# LAMEBOY.net
KiCad netlist of a schematic drawn in EAGLE
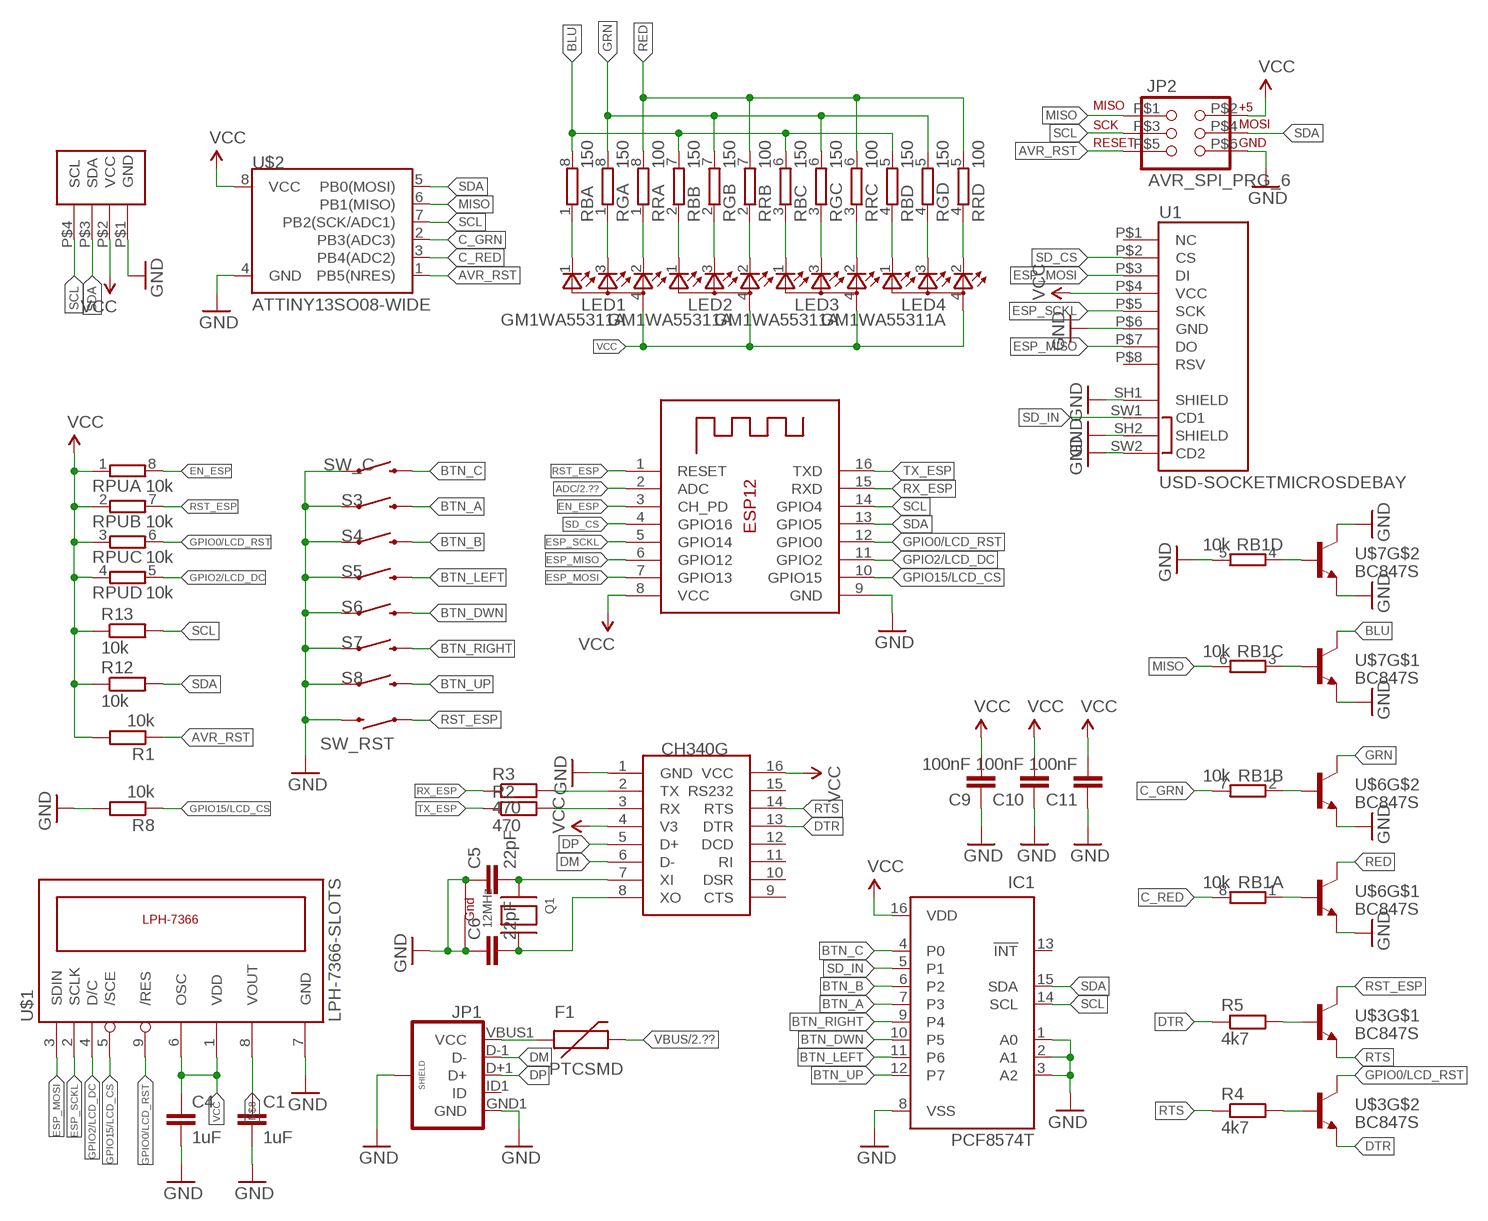
[diagram p0: schematic, sheet 1]
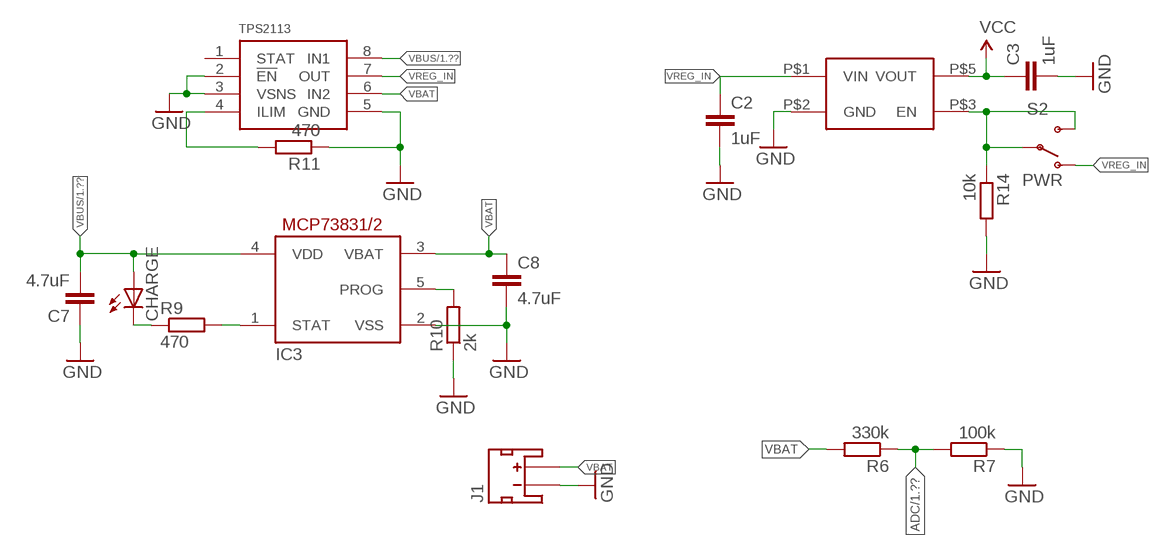
[diagram p1: schematic, sheet 2]

(export (version "E")
  (design (tool "Eeschema 10.0.6"))
  (components
    (comp (ref "C1")
      (value "1uF")
      (footprint "eagle-import:ONEFITSALL")
      (libsource (lib "eagle-import") (part "C-EUONEFITSALL"))
    )
    (comp (ref "C4")
      (value "1uF")
      (footprint "eagle-import:ONEFITSALL")
      (libsource (lib "eagle-import") (part "C-EUONEFITSALL"))
    )
    (comp (ref "C5")
      (value "22pF")
      (footprint "eagle-import:ONEFITSALL")
      (libsource (lib "eagle-import") (part "C-EUONEFITSALL"))
    )
    (comp (ref "C6")
      (value "22pF")
      (footprint "eagle-import:ONEFITSALL")
      (libsource (lib "eagle-import") (part "C-EUONEFITSALL"))
    )
    (comp (ref "C9")
      (value "100nF")
      (footprint "eagle-import:ONEFITSALL")
      (libsource (lib "eagle-import") (part "C-EUONEFITSALL"))
    )
    (comp (ref "C10")
      (value "100nF")
      (footprint "eagle-import:ONEFITSALL")
      (libsource (lib "eagle-import") (part "C-EUONEFITSALL"))
    )
    (comp (ref "C11")
      (value "100nF")
      (footprint "eagle-import:ONEFITSALL")
      (libsource (lib "eagle-import") (part "C-EUONEFITSALL"))
    )
    (comp (ref "CH340G")
      (value "CH340GCH340G")
      (footprint "eagle-import:SOIC16")
      (libsource (lib "eagle-import") (part "CH340GCH340G"))
    )
    (comp (ref "F1")
      (value "PTCSMD")
      (footprint "eagle-import:PTC-1206")
      (libsource (lib "eagle-import") (part "PTCSMD"))
    )
    (comp (ref "IC1")
      (value "PCF8574T")
      (footprint "eagle-import:SO16W")
      (fields (field (name "MPN") "PCF8574T/3,512"))
      (libsource (lib "eagle-import") (part "PCF8574T"))
    )
    (comp (ref "JP1")
      (value "USB_MICROB_PLUG-IDK")
      (footprint "eagle-import:USB-AB-MICRO-SMD_SLOT")
      (libsource (lib "eagle-import") (part "USB_MICROB_PLUG-IDK"))
    )
    (comp (ref "JP2")
      (value "AVR_SPI_PRG_6")
      (footprint "eagle-import:2X3_SMD_PAD")
      (libsource (lib "eagle-import") (part "AVR_SPI_PRG_6"))
    )
    (comp (ref "LED1")
      (value "GM1WA55311A")
      (footprint "eagle-import:GM1WA55311A")
      (libsource (lib "eagle-import") (part "GM1WA55311A"))
    )
    (comp (ref "LED2")
      (value "GM1WA55311A")
      (footprint "eagle-import:GM1WA55311A")
      (libsource (lib "eagle-import") (part "GM1WA55311A"))
    )
    (comp (ref "LED3")
      (value "GM1WA55311A")
      (footprint "eagle-import:GM1WA55311A")
      (libsource (lib "eagle-import") (part "GM1WA55311A"))
    )
    (comp (ref "LED4")
      (value "GM1WA55311A")
      (footprint "eagle-import:GM1WA55311A")
      (libsource (lib "eagle-import") (part "GM1WA55311A"))
    )
    (comp (ref "Q1")
      (value "12MHz")
      (footprint "eagle-import:NX3225_BIGGER")
      (libsource (lib "eagle-import") (part "XTAL-4BIGGER"))
    )
    (comp (ref "R1")
      (value "10k")
      (footprint "eagle-import:ONEFITSALL")
      (libsource (lib "eagle-import") (part "R-EU_ONEFITSALL"))
    )
    (comp (ref "R2")
      (value "470")
      (footprint "eagle-import:ONEFITSALL")
      (libsource (lib "eagle-import") (part "R-EU_ONEFITSALL"))
    )
    (comp (ref "R3")
      (value "470")
      (footprint "eagle-import:ONEFITSALL")
      (libsource (lib "eagle-import") (part "R-EU_ONEFITSALL"))
    )
    (comp (ref "R4")
      (value "4k7")
      (footprint "eagle-import:ONEFITSALL")
      (libsource (lib "eagle-import") (part "R-EU_ONEFITSALL"))
    )
    (comp (ref "R5")
      (value "4k7")
      (footprint "eagle-import:ONEFITSALL")
      (libsource (lib "eagle-import") (part "R-EU_ONEFITSALL"))
    )
    (comp (ref "R8")
      (value "10k")
      (footprint "eagle-import:ONEFITSALL")
      (libsource (lib "eagle-import") (part "R-EU_ONEFITSALL"))
    )
    (comp (ref "R12")
      (value "10k")
      (footprint "eagle-import:ONEFITSALL")
      (libsource (lib "eagle-import") (part "R-EU_ONEFITSALL"))
    )
    (comp (ref "R13")
      (value "10k")
      (footprint "eagle-import:ONEFITSALL")
      (libsource (lib "eagle-import") (part "R-EU_ONEFITSALL"))
    )
    (comp (ref "RB")
      (value "150")
      (footprint "eagle-import:0603-ARC")
      (libsource (lib "eagle-import") (part "4R-N0603-ARC"))
    )
    (comp (ref "RB1")
      (value "10k")
      (footprint "eagle-import:0603-ARC")
      (libsource (lib "eagle-import") (part "4R-N0603-ARC"))
    )
    (comp (ref "RG")
      (value "150")
      (footprint "eagle-import:0603-ARC")
      (libsource (lib "eagle-import") (part "4R-N0603-ARC"))
    )
    (comp (ref "RPU")
      (value "10k")
      (footprint "eagle-import:0603-ARC")
      (libsource (lib "eagle-import") (part "4R-N0603-ARC"))
    )
    (comp (ref "RR")
      (value "100")
      (footprint "eagle-import:0603-ARC")
      (libsource (lib "eagle-import") (part "4R-N0603-ARC"))
    )
    (comp (ref "S3")
      (value "SWITCH-MOMENTARY-2SMD-4")
      (footprint "eagle-import:TACTILE_SWITCH_TALL")
      (libsource (lib "eagle-import") (part "SWITCH-MOMENTARY-2SMD-4"))
    )
    (comp (ref "S4")
      (value "SWITCH-MOMENTARY-2SMD-4")
      (footprint "eagle-import:TACTILE_SWITCH_TALL")
      (libsource (lib "eagle-import") (part "SWITCH-MOMENTARY-2SMD-4"))
    )
    (comp (ref "S5")
      (value "SWITCH-MOMENTARY-2SMD-4")
      (footprint "eagle-import:TACTILE_SWITCH_TALL")
      (libsource (lib "eagle-import") (part "SWITCH-MOMENTARY-2SMD-4"))
    )
    (comp (ref "S6")
      (value "SWITCH-MOMENTARY-2SMD-4")
      (footprint "eagle-import:TACTILE_SWITCH_TALL")
      (libsource (lib "eagle-import") (part "SWITCH-MOMENTARY-2SMD-4"))
    )
    (comp (ref "S7")
      (value "SWITCH-MOMENTARY-2SMD-4")
      (footprint "eagle-import:TACTILE_SWITCH_TALL")
      (libsource (lib "eagle-import") (part "SWITCH-MOMENTARY-2SMD-4"))
    )
    (comp (ref "S8")
      (value "SWITCH-MOMENTARY-2SMD-4")
      (footprint "eagle-import:TACTILE_SWITCH_TALL")
      (libsource (lib "eagle-import") (part "SWITCH-MOMENTARY-2SMD-4"))
    )
    (comp (ref "SW_C")
      (value "SWITCH-MOMENTARY-2-SMD-1101NE")
      (footprint "eagle-import:TACTILE-SWITCH-1101NE")
      (libsource (lib "eagle-import") (part "SWITCH-MOMENTARY-2-SMD-1101NE"))
    )
    (comp (ref "SW_RST")
      (value "SWITCH-MOMENTARY-2-SMD-1101NE")
      (footprint "eagle-import:TACTILE-SWITCH-1101NE")
      (libsource (lib "eagle-import") (part "SWITCH-MOMENTARY-2-SMD-1101NE"))
    )
    (comp (ref "U$1")
      (value "LPH-7366-SLOTS")
      (footprint "eagle-import:LPH-7366-SLOTS")
      (libsource (lib "eagle-import") (part "LPH-7366-SLOTS"))
    )
    (comp (ref "U$2")
      (value "ATTINY13SO08-WIDE")
      (footprint "eagle-import:SO08-EIAJ")
      (libsource (lib "eagle-import") (part "ATTINY13SO08-WIDE"))
    )
    (comp (ref "U$3")
      (value "BC847S")
      (footprint "eagle-import:SOT363")
      (libsource (lib "eagle-import") (part "MMDT3904"))
    )
    (comp (ref "U$6")
      (value "BC847S")
      (footprint "eagle-import:SOT363")
      (libsource (lib "eagle-import") (part "MMDT3904"))
    )
    (comp (ref "U$7")
      (value "BC847S")
      (footprint "eagle-import:SOT363")
      (libsource (lib "eagle-import") (part "MMDT3904"))
    )
    (comp (ref "U$10")
      (value "I2C_GROVE")
      (footprint "eagle-import:I2C_GROVE")
      (libsource (lib "eagle-import") (part "I2C_GROVE"))
    )
    (comp (ref "U1")
      (value "USD-SOCKETMICROSDEBAY")
      (footprint "eagle-import:MICRO-SD-SOCKET-EBAY")
      (libsource (lib "eagle-import") (part "USD-SOCKETMICROSDEBAY"))
    )
    (comp (ref "X1")
      (value "ESP-12")
      (footprint "eagle-import:ESP-12")
      (libsource (lib "eagle-import") (part "ESP-12"))
    )
    (comp (ref "C2")
      (value "1uF")
      (footprint "eagle-import:ONEFITSALL")
      (libsource (lib "eagle-import") (part "C-EUONEFITSALL"))
    )
    (comp (ref "C3")
      (value "1uF")
      (footprint "eagle-import:ONEFITSALL")
      (libsource (lib "eagle-import") (part "C-EUONEFITSALL"))
    )
    (comp (ref "C7")
      (value "4.7uF")
      (footprint "eagle-import:ONEFITSALL")
      (libsource (lib "eagle-import") (part "C-EUONEFITSALL"))
    )
    (comp (ref "C8")
      (value "4.7uF")
      (footprint "eagle-import:ONEFITSALL")
      (libsource (lib "eagle-import") (part "C-EUONEFITSALL"))
    )
    (comp (ref "CHARGE")
      (value "LEDCHARLIE")
      (footprint "eagle-import:CHIPLED_0603_CHARLIE")
      (libsource (lib "eagle-import") (part "LEDCHARLIE"))
    )
    (comp (ref "IC3")
      (value "MCP73831")
      (footprint "eagle-import:SOT23-5L")
      (libsource (lib "eagle-import") (part "MCP73831/OT"))
    )
    (comp (ref "J1")
      (value "JST_2MM_MALE")
      (footprint "eagle-import:JST-2-SMD")
      (libsource (lib "eagle-import") (part "JST_2MM_MALE"))
    )
    (comp (ref "R6")
      (value "330k")
      (footprint "eagle-import:ONEFITSALL")
      (libsource (lib "eagle-import") (part "R-EU_ONEFITSALL"))
    )
    (comp (ref "R7")
      (value "100k")
      (footprint "eagle-import:ONEFITSALL")
      (libsource (lib "eagle-import") (part "R-EU_ONEFITSALL"))
    )
    (comp (ref "R9")
      (value "470")
      (footprint "eagle-import:ONEFITSALL")
      (libsource (lib "eagle-import") (part "R-EU_ONEFITSALL"))
    )
    (comp (ref "R10")
      (value "2k")
      (footprint "eagle-import:ONEFITSALL")
      (libsource (lib "eagle-import") (part "R-EU_ONEFITSALL"))
    )
    (comp (ref "R11")
      (value "470")
      (footprint "eagle-import:ONEFITSALL")
      (libsource (lib "eagle-import") (part "R-EU_ONEFITSALL"))
    )
    (comp (ref "R14")
      (value "10k")
      (footprint "eagle-import:ONEFITSALL")
      (libsource (lib "eagle-import") (part "R-EU_ONEFITSALL"))
    )
    (comp (ref "S2")
      (value "PWR")
      (footprint "eagle-import:SWITCH-SPST-SMD-A")
      (libsource (lib "eagle-import") (part "SWITCH-SPDT-SMD-A"))
    )
    (comp (ref "U$4")
      (value "TPS2113-PW")
      (footprint "eagle-import:TEXAS-PW")
      (libsource (lib "eagle-import") (part "TPS2113-PW"))
    )
    (comp (ref "U$9")
      (value "AP2112KAP2112K")
      (footprint "eagle-import:AP2112")
      (libsource (lib "eagle-import") (part "AP2112KAP2112K"))
    )
  )
  (nets
    (net (code "1") (name "ADC") (class "Default")
      (node (ref "R6") (pin "P$1") (pinfunction "1_P$1") (pintype "passive"))
      (node (ref "R7") (pin "P$2") (pinfunction "2_P$2") (pintype "passive"))
      (node (ref "X1") (pin "2") (pinfunction "ADC_2") (pintype "passive"))
    )
    (net (code "2") (name "AVR_RST") (class "Default")
      (node (ref "JP2") (pin "P$5") (pinfunction "5_P$5") (pintype "passive"))
      (node (ref "R1") (pin "P$1") (pinfunction "1_P$1") (pintype "passive"))
      (node (ref "U$2") (pin "1") (pinfunction "PB5(NRES)_1") (pintype "bidirectional"))
    )
    (net (code "3") (name "BLU") (class "Default")
      (node (ref "RB") (pin "5") (pinfunction "2_5") (pintype "passive"))
      (node (ref "RB") (pin "6") (pinfunction "2_6") (pintype "passive"))
      (node (ref "RB") (pin "7") (pinfunction "2_7") (pintype "passive"))
      (node (ref "RB") (pin "8") (pinfunction "2_8") (pintype "passive"))
      (node (ref "U$7") (pin "3") (pinfunction "C_3") (pintype "passive"))
    )
    (net (code "4") (name "BTN_A") (class "Default")
      (node (ref "IC1") (pin "7") (pinfunction "P3_7") (pintype "bidirectional"))
      (node (ref "S3") (pin "B2") (pinfunction "2_B2") (pintype "passive"))
    )
    (net (code "5") (name "BTN_B") (class "Default")
      (node (ref "IC1") (pin "6") (pinfunction "P2_6") (pintype "bidirectional"))
      (node (ref "S4") (pin "B2") (pinfunction "2_B2") (pintype "passive"))
    )
    (net (code "6") (name "BTN_C") (class "Default")
      (node (ref "IC1") (pin "4") (pinfunction "P0_4") (pintype "bidirectional"))
      (node (ref "SW_C") (pin "P$2") (pinfunction "2_P$2") (pintype "passive"))
    )
    (net (code "7") (name "BTN_DWN") (class "Default")
      (node (ref "IC1") (pin "10") (pinfunction "P5_10") (pintype "bidirectional"))
      (node (ref "S6") (pin "B2") (pinfunction "2_B2") (pintype "passive"))
    )
    (net (code "8") (name "BTN_LEFT") (class "Default")
      (node (ref "IC1") (pin "11") (pinfunction "P6_11") (pintype "bidirectional"))
      (node (ref "S5") (pin "B2") (pinfunction "2_B2") (pintype "passive"))
    )
    (net (code "9") (name "BTN_RIGHT") (class "Default")
      (node (ref "IC1") (pin "9") (pinfunction "P4_9") (pintype "bidirectional"))
      (node (ref "S7") (pin "B2") (pinfunction "2_B2") (pintype "passive"))
    )
    (net (code "10") (name "BTN_UP") (class "Default")
      (node (ref "IC1") (pin "12") (pinfunction "P7_12") (pintype "bidirectional"))
      (node (ref "S8") (pin "B2") (pinfunction "2_B2") (pintype "passive"))
    )
    (net (code "11") (name "C_GRN") (class "Default")
      (node (ref "RB1") (pin "7") (pinfunction "2_7") (pintype "passive"))
      (node (ref "U$2") (pin "2") (pinfunction "PB3(ADC3)_2") (pintype "bidirectional"))
    )
    (net (code "12") (name "C_RED") (class "Default")
      (node (ref "RB1") (pin "8") (pinfunction "2_8") (pintype "passive"))
      (node (ref "U$2") (pin "3") (pinfunction "PB4(ADC2)_3") (pintype "bidirectional"))
    )
    (net (code "13") (name "DM") (class "Default")
      (node (ref "CH340G") (pin "6") (pinfunction "D-_6") (pintype "bidirectional"))
      (node (ref "JP1") (pin "D-1") (pinfunction "D-_D-1") (pintype "bidirectional"))
    )
    (net (code "14") (name "DP") (class "Default")
      (node (ref "CH340G") (pin "5") (pinfunction "D+_5") (pintype "bidirectional"))
      (node (ref "JP1") (pin "D+1") (pinfunction "D+_D+1") (pintype "bidirectional"))
    )
    (net (code "15") (name "DTR") (class "Default")
      (node (ref "CH340G") (pin "13") (pinfunction "DTR_13") (pintype "bidirectional"))
      (node (ref "R5") (pin "P$1") (pinfunction "1_P$1") (pintype "passive"))
      (node (ref "U$3") (pin "1") (pinfunction "E_1") (pintype "passive"))
    )
    (net (code "16") (name "EN_ESP") (class "Default")
      (node (ref "RPU") (pin "8") (pinfunction "2_8") (pintype "passive"))
      (node (ref "X1") (pin "3") (pinfunction "CH_PD_3") (pintype "input"))
    )
    (net (code "17") (name "ESP_MISO") (class "Default")
      (node (ref "U1") (pin "P$7") (pinfunction "DO_P$7") (pintype "bidirectional"))
      (node (ref "X1") (pin "6") (pinfunction "GPIO12_6") (pintype "bidirectional"))
    )
    (net (code "18") (name "ESP_MOSI") (class "Default")
      (node (ref "U$1") (pin "3") (pinfunction "SDIN_3") (pintype "input"))
      (node (ref "U1") (pin "P$3") (pinfunction "DI_P$3") (pintype "bidirectional"))
      (node (ref "X1") (pin "7") (pinfunction "GPIO13_7") (pintype "bidirectional"))
    )
    (net (code "19") (name "ESP_SCKL") (class "Default")
      (node (ref "U$1") (pin "2") (pinfunction "SCLK_2") (pintype "input"))
      (node (ref "U1") (pin "P$5") (pinfunction "SCK_P$5") (pintype "bidirectional"))
      (node (ref "X1") (pin "5") (pinfunction "GPIO14_5") (pintype "bidirectional"))
    )
    (net (code "20") (name "GND") (class "Default")
      (node (ref "C1") (pin "P$2") (pinfunction "2_P$2") (pintype "passive"))
      (node (ref "C10") (pin "P$1") (pinfunction "1_P$1") (pintype "passive"))
      (node (ref "C11") (pin "P$1") (pinfunction "1_P$1") (pintype "passive"))
      (node (ref "C2") (pin "P$2") (pinfunction "2_P$2") (pintype "passive"))
      (node (ref "C3") (pin "P$2") (pinfunction "2_P$2") (pintype "passive"))
      (node (ref "C4") (pin "P$2") (pinfunction "2_P$2") (pintype "passive"))
      (node (ref "C5") (pin "P$1") (pinfunction "1_P$1") (pintype "passive"))
      (node (ref "C6") (pin "P$1") (pinfunction "1_P$1") (pintype "passive"))
      (node (ref "C7") (pin "P$1") (pinfunction "1_P$1") (pintype "passive"))
      (node (ref "C8") (pin "P$2") (pinfunction "2_P$2") (pintype "passive"))
      (node (ref "C9") (pin "P$1") (pinfunction "1_P$1") (pintype "passive"))
      (node (ref "CH340G") (pin "1") (pinfunction "GND_1") (pintype "bidirectional"))
      (node (ref "IC1") (pin "1") (pinfunction "A0_1") (pintype "input"))
      (node (ref "IC1") (pin "2") (pinfunction "A1_2") (pintype "input"))
      (node (ref "IC1") (pin "3") (pinfunction "A2_3") (pintype "input"))
      (node (ref "IC1") (pin "8") (pinfunction "VSS_8") (pintype "power_in"))
      (node (ref "IC3") (pin "2") (pinfunction "VSS_2") (pintype "power_in"))
      (node (ref "J1") (pin "1") (pinfunction "-_1") (pintype "bidirectional"))
      (node (ref "JP1") (pin "GND1") (pinfunction "GND_GND1") (pintype "bidirectional"))
      (node (ref "JP1") (pin "P$1") (pinfunction "SHIELD_P$1") (pintype "bidirectional"))
      (node (ref "JP1") (pin "P$2") (pinfunction "SHIELD_P$2") (pintype "bidirectional"))
      (node (ref "JP1") (pin "P$3") (pinfunction "SHIELD_P$3") (pintype "bidirectional"))
      (node (ref "JP1") (pin "P$4") (pinfunction "SHIELD_P$4") (pintype "bidirectional"))
      (node (ref "JP2") (pin "P$6") (pinfunction "6_P$6") (pintype "passive"))
      (node (ref "Q1") (pin "2") (pinfunction "G2_2") (pintype "power_in"))
      (node (ref "Q1") (pin "4") (pinfunction "G1_4") (pintype "power_in"))
      (node (ref "R10") (pin "P$1") (pinfunction "1_P$1") (pintype "passive"))
      (node (ref "R11") (pin "P$1") (pinfunction "1_P$1") (pintype "passive"))
      (node (ref "R14") (pin "P$2") (pinfunction "2_P$2") (pintype "passive"))
      (node (ref "R7") (pin "P$1") (pinfunction "1_P$1") (pintype "passive"))
      (node (ref "R8") (pin "P$2") (pinfunction "2_P$2") (pintype "passive"))
      (node (ref "RB1") (pin "5") (pinfunction "2_5") (pintype "passive"))
      (node (ref "S3") (pin "A2") (pinfunction "1_A2") (pintype "passive"))
      (node (ref "S4") (pin "A2") (pinfunction "1_A2") (pintype "passive"))
      (node (ref "S5") (pin "A2") (pinfunction "1_A2") (pintype "passive"))
      (node (ref "S6") (pin "A2") (pinfunction "1_A2") (pintype "passive"))
      (node (ref "S7") (pin "A2") (pinfunction "1_A2") (pintype "passive"))
      (node (ref "S8") (pin "A2") (pinfunction "1_A2") (pintype "passive"))
      (node (ref "SW_C") (pin "P$1") (pinfunction "1_P$1") (pintype "passive"))
      (node (ref "SW_RST") (pin "P$2") (pinfunction "2_P$2") (pintype "passive"))
      (node (ref "U$1") (pin "7") (pinfunction "GND_7") (pintype "power_in"))
      (node (ref "U$10") (pin "P$1") (pinfunction "GND_P$1") (pintype "bidirectional"))
      (node (ref "U$2") (pin "4") (pinfunction "GND_4") (pintype "bidirectional"))
      (node (ref "U$4") (pin "2") (pinfunction "~{EN}_2") (pintype "bidirectional"))
      (node (ref "U$4") (pin "3") (pinfunction "VSNS_3") (pintype "bidirectional"))
      (node (ref "U$4") (pin "5") (pinfunction "GND_5") (pintype "bidirectional"))
      (node (ref "U$6") (pin "1") (pinfunction "E_1") (pintype "passive"))
      (node (ref "U$6") (pin "4") (pinfunction "E_4") (pintype "passive"))
      (node (ref "U$7") (pin "1") (pinfunction "E_1") (pintype "passive"))
      (node (ref "U$7") (pin "4") (pinfunction "E_4") (pintype "passive"))
      (node (ref "U$7") (pin "6") (pinfunction "C_6") (pintype "passive"))
      (node (ref "U$9") (pin "P$2") (pinfunction "GND_P$2") (pintype "bidirectional"))
      (node (ref "U1") (pin "P$6") (pinfunction "GND_P$6") (pintype "bidirectional"))
      (node (ref "U1") (pin "SH1") (pinfunction "SHIELD_SH1") (pintype "bidirectional"))
      (node (ref "U1") (pin "SH2") (pinfunction "SHIELD_SH2") (pintype "bidirectional"))
      (node (ref "U1") (pin "SW2") (pinfunction "CD2_SW2") (pintype "bidirectional"))
      (node (ref "X1") (pin "9") (pinfunction "GND_9") (pintype "power_in"))
    )
    (net (code "21") (name "GPIO0{slash}LCD_RST") (class "Default")
      (node (ref "RPU") (pin "6") (pinfunction "2_6") (pintype "passive"))
      (node (ref "U$1") (pin "9") (pinfunction "/RES_9") (pintype "input"))
      (node (ref "U$3") (pin "6") (pinfunction "C_6") (pintype "passive"))
      (node (ref "X1") (pin "12") (pinfunction "GPIO0_12") (pintype "bidirectional"))
    )
    (net (code "22") (name "GPIO2{slash}LCD_DC") (class "Default")
      (node (ref "RPU") (pin "5") (pinfunction "2_5") (pintype "passive"))
      (node (ref "U$1") (pin "4") (pinfunction "D/C_4") (pintype "input"))
      (node (ref "X1") (pin "11") (pinfunction "GPIO2_11") (pintype "bidirectional"))
    )
    (net (code "23") (name "GPIO15{slash}LCD_CS") (class "Default")
      (node (ref "R8") (pin "P$1") (pinfunction "1_P$1") (pintype "passive"))
      (node (ref "U$1") (pin "5") (pinfunction "/SCE_5") (pintype "input"))
      (node (ref "X1") (pin "10") (pinfunction "GPIO15_10") (pintype "bidirectional"))
    )
    (net (code "24") (name "GRN") (class "Default")
      (node (ref "RG") (pin "5") (pinfunction "2_5") (pintype "passive"))
      (node (ref "RG") (pin "6") (pinfunction "2_6") (pintype "passive"))
      (node (ref "RG") (pin "7") (pinfunction "2_7") (pintype "passive"))
      (node (ref "RG") (pin "8") (pinfunction "2_8") (pintype "passive"))
      (node (ref "U$6") (pin "6") (pinfunction "C_6") (pintype "passive"))
    )
    (net (code "25") (name "MISO") (class "Default")
      (node (ref "JP2") (pin "P$1") (pinfunction "1_P$1") (pintype "passive"))
      (node (ref "RB1") (pin "6") (pinfunction "2_6") (pintype "passive"))
      (node (ref "U$2") (pin "6") (pinfunction "PB1(MISO)_6") (pintype "bidirectional"))
    )
    (net (code "26") (name "N$8") (class "Default")
      (node (ref "C1") (pin "P$1") (pinfunction "1_P$1") (pintype "passive"))
      (node (ref "U$1") (pin "8") (pinfunction "VOUT_8") (pintype "passive"))
    )
    (net (code "27") (name "Net-(C5-2)") (class "Default")
      (node (ref "C5") (pin "P$2") (pinfunction "2_P$2") (pintype "passive"))
      (node (ref "CH340G") (pin "7") (pinfunction "XI_7") (pintype "bidirectional"))
      (node (ref "Q1") (pin "1") (pinfunction "X1_1") (pintype "bidirectional"))
    )
    (net (code "28") (name "Net-(C6-2)") (class "Default")
      (node (ref "C6") (pin "P$2") (pinfunction "2_P$2") (pintype "passive"))
      (node (ref "CH340G") (pin "8") (pinfunction "XO_8") (pintype "bidirectional"))
      (node (ref "Q1") (pin "3") (pinfunction "X2_3") (pintype "bidirectional"))
    )
    (net (code "29") (name "Net-(CH340G-RX)") (class "Default")
      (node (ref "CH340G") (pin "3") (pinfunction "RX_3") (pintype "bidirectional"))
      (node (ref "R2") (pin "P$2") (pinfunction "2_P$2") (pintype "passive"))
    )
    (net (code "30") (name "Net-(CH340G-TX)") (class "Default")
      (node (ref "CH340G") (pin "2") (pinfunction "TX_2") (pintype "bidirectional"))
      (node (ref "R3") (pin "P$2") (pinfunction "2_P$2") (pintype "passive"))
    )
    (net (code "31") (name "Net-(IC3-PROG)") (class "Default")
      (node (ref "IC3") (pin "5") (pinfunction "PROG_5") (pintype "input"))
      (node (ref "R10") (pin "P$2") (pinfunction "2_P$2") (pintype "passive"))
    )
    (net (code "32") (name "Net-(IC3-STAT)") (class "Default")
      (node (ref "IC3") (pin "1") (pinfunction "STAT_1") (pintype "output"))
      (node (ref "R9") (pin "P$2") (pinfunction "2_P$2") (pintype "passive"))
    )
    (net (code "33") (name "Net-(JP1-VCC)") (class "Default")
      (node (ref "F1") (pin "1") (pinfunction "1_1") (pintype "bidirectional"))
      (node (ref "JP1") (pin "VBUS1") (pinfunction "VCC_VBUS1") (pintype "bidirectional"))
    )
    (net (code "34") (name "Net-(LED1-CBLUE)") (class "Default")
      (node (ref "LED1") (pin "3") (pinfunction "CBLUE_3") (pintype "passive"))
      (node (ref "RG") (pin "1") (pinfunction "1_1") (pintype "passive"))
    )
    (net (code "35") (name "Net-(LED1-CGREEN)") (class "Default")
      (node (ref "LED1") (pin "1") (pinfunction "CGREEN_1") (pintype "passive"))
      (node (ref "RB") (pin "1") (pinfunction "1_1") (pintype "passive"))
    )
    (net (code "36") (name "Net-(LED1-CRED)") (class "Default")
      (node (ref "LED1") (pin "2") (pinfunction "CRED_2") (pintype "passive"))
      (node (ref "RR") (pin "1") (pinfunction "1_1") (pintype "passive"))
    )
    (net (code "37") (name "Net-(LED2-CBLUE)") (class "Default")
      (node (ref "LED2") (pin "3") (pinfunction "CBLUE_3") (pintype "passive"))
      (node (ref "RG") (pin "2") (pinfunction "1_2") (pintype "passive"))
    )
    (net (code "38") (name "Net-(LED2-CGREEN)") (class "Default")
      (node (ref "LED2") (pin "1") (pinfunction "CGREEN_1") (pintype "passive"))
      (node (ref "RB") (pin "2") (pinfunction "1_2") (pintype "passive"))
    )
    (net (code "39") (name "Net-(LED2-CRED)") (class "Default")
      (node (ref "LED2") (pin "2") (pinfunction "CRED_2") (pintype "passive"))
      (node (ref "RR") (pin "2") (pinfunction "1_2") (pintype "passive"))
    )
    (net (code "40") (name "Net-(LED3-CBLUE)") (class "Default")
      (node (ref "LED3") (pin "3") (pinfunction "CBLUE_3") (pintype "passive"))
      (node (ref "RG") (pin "3") (pinfunction "1_3") (pintype "passive"))
    )
    (net (code "41") (name "Net-(LED3-CGREEN)") (class "Default")
      (node (ref "LED3") (pin "1") (pinfunction "CGREEN_1") (pintype "passive"))
      (node (ref "RB") (pin "3") (pinfunction "1_3") (pintype "passive"))
    )
    (net (code "42") (name "Net-(LED3-CRED)") (class "Default")
      (node (ref "LED3") (pin "2") (pinfunction "CRED_2") (pintype "passive"))
      (node (ref "RR") (pin "3") (pinfunction "1_3") (pintype "passive"))
    )
    (net (code "43") (name "Net-(LED4-CBLUE)") (class "Default")
      (node (ref "LED4") (pin "3") (pinfunction "CBLUE_3") (pintype "passive"))
      (node (ref "RG") (pin "4") (pinfunction "1_4") (pintype "passive"))
    )
    (net (code "44") (name "Net-(LED4-CGREEN)") (class "Default")
      (node (ref "LED4") (pin "1") (pinfunction "CGREEN_1") (pintype "passive"))
      (node (ref "RB") (pin "4") (pinfunction "1_4") (pintype "passive"))
    )
    (net (code "45") (name "Net-(LED4-CRED)") (class "Default")
      (node (ref "LED4") (pin "2") (pinfunction "CRED_2") (pintype "passive"))
      (node (ref "RR") (pin "4") (pinfunction "1_4") (pintype "passive"))
    )
    (net (code "46") (name "Net-(R4-2)") (class "Default")
      (node (ref "R4") (pin "P$2") (pinfunction "2_P$2") (pintype "passive"))
      (node (ref "U$3") (pin "2") (pinfunction "B_2") (pintype "passive"))
    )
    (net (code "47") (name "Net-(R5-2)") (class "Default")
      (node (ref "R5") (pin "P$2") (pinfunction "2_P$2") (pintype "passive"))
      (node (ref "U$3") (pin "5") (pinfunction "B_5") (pintype "passive"))
    )
    (net (code "48") (name "Net-(R9-1)") (class "Default")
      (node (ref "CHARGE") (pin "C") (pinfunction "C_C") (pintype "passive"))
      (node (ref "R9") (pin "P$1") (pinfunction "1_P$1") (pintype "passive"))
    )
    (net (code "49") (name "Net-(R11-2)") (class "Default")
      (node (ref "R11") (pin "P$2") (pinfunction "2_P$2") (pintype "passive"))
      (node (ref "U$4") (pin "4") (pinfunction "ILIM_4") (pintype "bidirectional"))
    )
    (net (code "50") (name "Net-(R14-1)") (class "Default")
      (node (ref "R14") (pin "P$1") (pinfunction "1_P$1") (pintype "passive"))
      (node (ref "S2") (pin "2") (pinfunction "P_2") (pintype "passive"))
      (node (ref "S2") (pin "3") (pinfunction "S_3") (pintype "passive"))
      (node (ref "U$9") (pin "P$3") (pinfunction "EN_P$3") (pintype "bidirectional"))
    )
    (net (code "51") (name "Net-(RB1B-1)") (class "Default")
      (node (ref "RB1") (pin "2") (pinfunction "1_2") (pintype "passive"))
      (node (ref "U$6") (pin "2") (pinfunction "B_2") (pintype "passive"))
    )
    (net (code "52") (name "Net-(RB1C-1)") (class "Default")
      (node (ref "RB1") (pin "3") (pinfunction "1_3") (pintype "passive"))
      (node (ref "U$7") (pin "5") (pinfunction "B_5") (pintype "passive"))
    )
    (net (code "53") (name "Net-(RB1D-1)") (class "Default")
      (node (ref "RB1") (pin "4") (pinfunction "1_4") (pintype "passive"))
      (node (ref "U$7") (pin "2") (pinfunction "B_2") (pintype "passive"))
    )
    (net (code "54") (name "Net-(U$6A-B)") (class "Default")
      (node (ref "RB1") (pin "1") (pinfunction "1_1") (pintype "passive"))
      (node (ref "U$6") (pin "5") (pinfunction "B_5") (pintype "passive"))
    )
    (net (code "55") (name "RED") (class "Default")
      (node (ref "RR") (pin "5") (pinfunction "2_5") (pintype "passive"))
      (node (ref "RR") (pin "6") (pinfunction "2_6") (pintype "passive"))
      (node (ref "RR") (pin "7") (pinfunction "2_7") (pintype "passive"))
      (node (ref "RR") (pin "8") (pinfunction "2_8") (pintype "passive"))
      (node (ref "U$6") (pin "3") (pinfunction "C_3") (pintype "passive"))
    )
    (net (code "56") (name "RST_ESP") (class "Default")
      (node (ref "RPU") (pin "7") (pinfunction "2_7") (pintype "passive"))
      (node (ref "SW_RST") (pin "P$1") (pinfunction "1_P$1") (pintype "passive"))
      (node (ref "U$3") (pin "3") (pinfunction "C_3") (pintype "passive"))
      (node (ref "X1") (pin "1") (pinfunction "RESET_1") (pintype "input"))
    )
    (net (code "57") (name "RTS") (class "Default")
      (node (ref "CH340G") (pin "14") (pinfunction "RTS_14") (pintype "bidirectional"))
      (node (ref "R4") (pin "P$1") (pinfunction "1_P$1") (pintype "passive"))
      (node (ref "U$3") (pin "4") (pinfunction "E_4") (pintype "passive"))
    )
    (net (code "58") (name "RX_ESP") (class "Default")
      (node (ref "R3") (pin "P$1") (pinfunction "1_P$1") (pintype "passive"))
      (node (ref "X1") (pin "15") (pinfunction "RXD_15") (pintype "input"))
    )
    (net (code "59") (name "SCL") (class "Default")
      (node (ref "IC1") (pin "14") (pinfunction "SCL_14") (pintype "input"))
      (node (ref "JP2") (pin "P$3") (pinfunction "3_P$3") (pintype "passive"))
      (node (ref "R13") (pin "P$2") (pinfunction "2_P$2") (pintype "passive"))
      (node (ref "U$10") (pin "P$4") (pinfunction "SCL_P$4") (pintype "bidirectional"))
      (node (ref "U$2") (pin "7") (pinfunction "PB2(SCK/ADC1)_7") (pintype "bidirectional"))
      (node (ref "X1") (pin "14") (pinfunction "GPIO4_14") (pintype "bidirectional"))
    )
    (net (code "60") (name "SDA") (class "Default")
      (node (ref "IC1") (pin "15") (pinfunction "SDA_15") (pintype "bidirectional"))
      (node (ref "JP2") (pin "P$4") (pinfunction "4_P$4") (pintype "passive"))
      (node (ref "R12") (pin "P$2") (pinfunction "2_P$2") (pintype "passive"))
      (node (ref "U$10") (pin "P$3") (pinfunction "SDA_P$3") (pintype "bidirectional"))
      (node (ref "U$2") (pin "5") (pinfunction "PB0(MOSI)_5") (pintype "bidirectional"))
      (node (ref "X1") (pin "13") (pinfunction "GPIO5_13") (pintype "bidirectional"))
    )
    (net (code "61") (name "SD_CS") (class "Default")
      (node (ref "U1") (pin "P$2") (pinfunction "CS_P$2") (pintype "bidirectional"))
      (node (ref "X1") (pin "4") (pinfunction "GPIO16_4") (pintype "bidirectional"))
    )
    (net (code "62") (name "SD_IN") (class "Default")
      (node (ref "IC1") (pin "5") (pinfunction "P1_5") (pintype "bidirectional"))
      (node (ref "U1") (pin "SW1") (pinfunction "CD1_SW1") (pintype "bidirectional"))
    )
    (net (code "63") (name "TX_ESP") (class "Default")
      (node (ref "R2") (pin "P$1") (pinfunction "1_P$1") (pintype "passive"))
      (node (ref "X1") (pin "16") (pinfunction "TXD_16") (pintype "output"))
    )
    (net (code "64") (name "VBAT") (class "Default")
      (node (ref "C8") (pin "P$1") (pinfunction "1_P$1") (pintype "passive"))
      (node (ref "IC3") (pin "3") (pinfunction "VBAT_3") (pintype "bidirectional"))
      (node (ref "J1") (pin "2") (pinfunction "+_2") (pintype "bidirectional"))
      (node (ref "R6") (pin "P$2") (pinfunction "2_P$2") (pintype "passive"))
      (node (ref "U$4") (pin "6") (pinfunction "IN2_6") (pintype "bidirectional"))
    )
    (net (code "65") (name "VBUS") (class "Default")
      (node (ref "C7") (pin "P$2") (pinfunction "2_P$2") (pintype "passive"))
      (node (ref "CHARGE") (pin "A") (pinfunction "A_A") (pintype "passive"))
      (node (ref "F1") (pin "2") (pinfunction "2_2") (pintype "bidirectional"))
      (node (ref "IC3") (pin "4") (pinfunction "VDD_4") (pintype "power_in"))
      (node (ref "U$4") (pin "8") (pinfunction "IN1_8") (pintype "bidirectional"))
    )
    (net (code "66") (name "VCC") (class "Default")
      (node (ref "C10") (pin "P$2") (pinfunction "2_P$2") (pintype "passive"))
      (node (ref "C11") (pin "P$2") (pinfunction "2_P$2") (pintype "passive"))
      (node (ref "C3") (pin "P$1") (pinfunction "1_P$1") (pintype "passive"))
      (node (ref "C4") (pin "P$1") (pinfunction "1_P$1") (pintype "passive"))
      (node (ref "C9") (pin "P$2") (pinfunction "2_P$2") (pintype "passive"))
      (node (ref "CH340G") (pin "16") (pinfunction "VCC_16") (pintype "bidirectional"))
      (node (ref "CH340G") (pin "4") (pinfunction "V3_4") (pintype "bidirectional"))
      (node (ref "IC1") (pin "16") (pinfunction "VDD_16") (pintype "power_in"))
      (node (ref "JP2") (pin "P$2") (pinfunction "2_P$2") (pintype "passive"))
      (node (ref "LED1") (pin "4") (pinfunction "A_4") (pintype "passive"))
      (node (ref "LED2") (pin "4") (pinfunction "A_4") (pintype "passive"))
      (node (ref "LED3") (pin "4") (pinfunction "A_4") (pintype "passive"))
      (node (ref "LED4") (pin "4") (pinfunction "A_4") (pintype "passive"))
      (node (ref "R1") (pin "P$2") (pinfunction "2_P$2") (pintype "passive"))
      (node (ref "R12") (pin "P$1") (pinfunction "1_P$1") (pintype "passive"))
      (node (ref "R13") (pin "P$1") (pinfunction "1_P$1") (pintype "passive"))
      (node (ref "RPU") (pin "1") (pinfunction "1_1") (pintype "passive"))
      (node (ref "RPU") (pin "2") (pinfunction "1_2") (pintype "passive"))
      (node (ref "RPU") (pin "3") (pinfunction "1_3") (pintype "passive"))
      (node (ref "RPU") (pin "4") (pinfunction "1_4") (pintype "passive"))
      (node (ref "U$1") (pin "1") (pinfunction "VDD_1") (pintype "power_in"))
      (node (ref "U$1") (pin "6") (pinfunction "OSC_6") (pintype "passive"))
      (node (ref "U$10") (pin "P$2") (pinfunction "VCC_P$2") (pintype "bidirectional"))
      (node (ref "U$2") (pin "8") (pinfunction "VCC_8") (pintype "bidirectional"))
      (node (ref "U$9") (pin "P$5") (pinfunction "VOUT_P$5") (pintype "bidirectional"))
      (node (ref "U1") (pin "P$4") (pinfunction "VCC_P$4") (pintype "bidirectional"))
      (node (ref "X1") (pin "8") (pinfunction "VCC_8") (pintype "power_in"))
    )
    (net (code "67") (name "VREG_IN") (class "Default")
      (node (ref "C2") (pin "P$1") (pinfunction "1_P$1") (pintype "passive"))
      (node (ref "S2") (pin "1") (pinfunction "O_1") (pintype "passive"))
      (node (ref "U$4") (pin "7") (pinfunction "OUT_7") (pintype "bidirectional"))
      (node (ref "U$9") (pin "P$1") (pinfunction "VIN_P$1") (pintype "bidirectional"))
    )
    (net (code "68") (name "unconnected-(CH340G-CTS-Pad9)") (class "Default")
      (node (ref "CH340G") (pin "9") (pinfunction "CTS_9") (pintype "bidirectional"))
    )
    (net (code "69") (name "unconnected-(CH340G-DCD-Pad12)") (class "Default")
      (node (ref "CH340G") (pin "12") (pinfunction "DCD_12") (pintype "bidirectional"))
    )
    (net (code "70") (name "unconnected-(CH340G-DSR-Pad10)") (class "Default")
      (node (ref "CH340G") (pin "10") (pinfunction "DSR_10") (pintype "bidirectional"))
    )
    (net (code "71") (name "unconnected-(CH340G-RI-Pad11)") (class "Default")
      (node (ref "CH340G") (pin "11") (pinfunction "RI_11") (pintype "bidirectional"))
    )
    (net (code "72") (name "unconnected-(CH340G-RS232-Pad15)") (class "Default")
      (node (ref "CH340G") (pin "15") (pinfunction "RS232_15") (pintype "bidirectional"))
    )
    (net (code "73") (name "unconnected-(IC1-~{INT}-Pad13)") (class "Default")
      (node (ref "IC1") (pin "13") (pinfunction "~{INT}_13") (pintype "output"))
    )
    (net (code "74") (name "unconnected-(J1-PAD1-PadNC1)") (class "Default")
      (node (ref "J1") (pin "NC1") (pinfunction "PAD1_NC1") (pintype "bidirectional"))
    )
    (net (code "75") (name "unconnected-(J1-PAD2-PadNC2)") (class "Default")
      (node (ref "J1") (pin "NC2") (pinfunction "PAD2_NC2") (pintype "bidirectional"))
    )
    (net (code "76") (name "unconnected-(JP1-ID-PadID1)") (class "Default")
      (node (ref "JP1") (pin "ID1") (pinfunction "ID_ID1") (pintype "bidirectional"))
    )
    (net (code "77") (name "unconnected-(U$4-STAT-Pad1)") (class "Default")
      (node (ref "U$4") (pin "1") (pinfunction "STAT_1") (pintype "bidirectional"))
    )
    (net (code "78") (name "unconnected-(U1-NC-PadP$1)") (class "Default")
      (node (ref "U1") (pin "P$1") (pinfunction "NC_P$1") (pintype "bidirectional"))
    )
    (net (code "79") (name "unconnected-(U1-RSV-PadP$8)") (class "Default")
      (node (ref "U1") (pin "P$8") (pinfunction "RSV_P$8") (pintype "bidirectional"))
    )
  )
)
